# year-led-r1.net
KiCad netlist of a schematic drawn in EAGLE
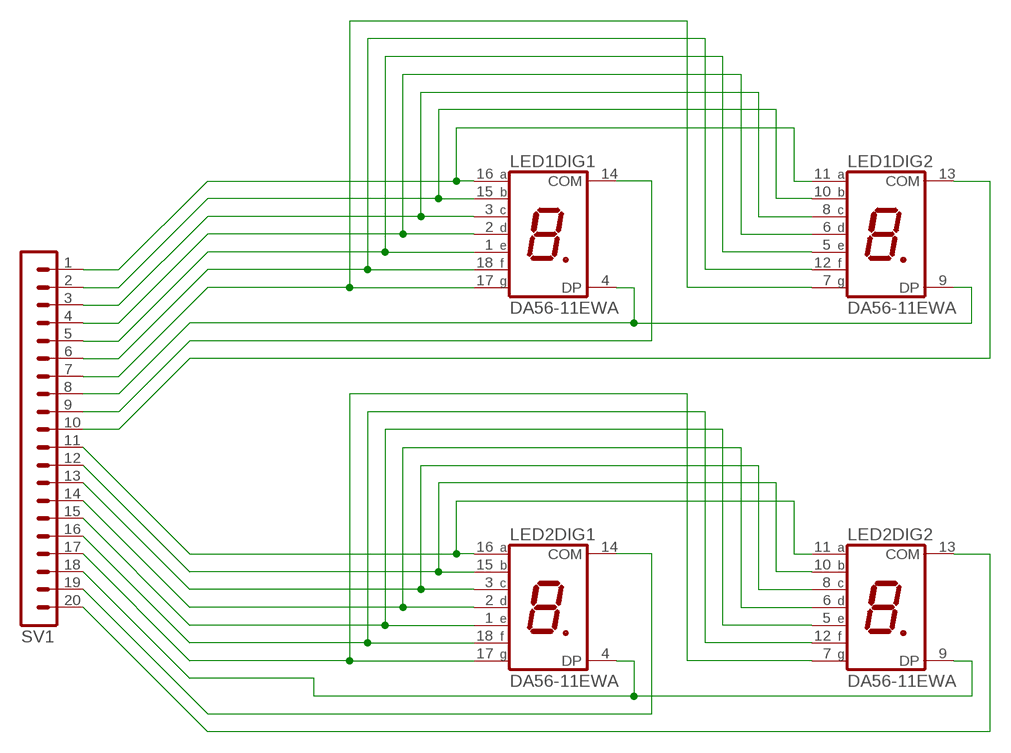
[diagram p0: schematic, sheet 1]

(export (version "E")
  (design (tool "Eeschema 10.0.6"))
  (components
    (comp (ref "LED1")
      (value "DA56-11EWA")
      (footprint "eagle-import:DA56")
      (libsource (lib "eagle-import") (part "DA56-11EWA"))
    )
    (comp (ref "LED2")
      (value "DA56-11EWA")
      (footprint "eagle-import:DA56")
      (libsource (lib "eagle-import") (part "DA56-11EWA"))
    )
    (comp (ref "SV1")
      (value "MA20-1W")
      (footprint "eagle-import:MA20-1W")
      (libsource (lib "eagle-import") (part "MA20-1W"))
    )
  )
  (nets
    (net (code "1") (name "Net-(LED1A-A)") (class "Default")
      (node (ref "LED1") (pin "11") (pinfunction "A_11") (pintype "passive"))
      (node (ref "LED1") (pin "16") (pinfunction "A_16") (pintype "passive"))
      (node (ref "SV1") (pin "1") (pinfunction "1_1") (pintype "passive"))
    )
    (net (code "2") (name "Net-(LED1A-B)") (class "Default")
      (node (ref "LED1") (pin "10") (pinfunction "B_10") (pintype "passive"))
      (node (ref "LED1") (pin "15") (pinfunction "B_15") (pintype "passive"))
      (node (ref "SV1") (pin "2") (pinfunction "2_2") (pintype "passive"))
    )
    (net (code "3") (name "Net-(LED1A-C)") (class "Default")
      (node (ref "LED1") (pin "3") (pinfunction "C_3") (pintype "passive"))
      (node (ref "LED1") (pin "8") (pinfunction "C_8") (pintype "passive"))
      (node (ref "SV1") (pin "3") (pinfunction "3_3") (pintype "passive"))
    )
    (net (code "4") (name "Net-(LED1A-COM)") (class "Default")
      (node (ref "LED1") (pin "14") (pinfunction "COM_14") (pintype "passive"))
      (node (ref "SV1") (pin "9") (pinfunction "9_9") (pintype "passive"))
    )
    (net (code "5") (name "Net-(LED1A-D)") (class "Default")
      (node (ref "LED1") (pin "2") (pinfunction "D_2") (pintype "passive"))
      (node (ref "LED1") (pin "6") (pinfunction "D_6") (pintype "passive"))
      (node (ref "SV1") (pin "4") (pinfunction "4_4") (pintype "passive"))
    )
    (net (code "6") (name "Net-(LED1A-DP)") (class "Default")
      (node (ref "LED1") (pin "4") (pinfunction "DP_4") (pintype "passive"))
      (node (ref "LED1") (pin "9") (pinfunction "DP_9") (pintype "passive"))
      (node (ref "SV1") (pin "8") (pinfunction "8_8") (pintype "passive"))
    )
    (net (code "7") (name "Net-(LED1A-E)") (class "Default")
      (node (ref "LED1") (pin "1") (pinfunction "E_1") (pintype "passive"))
      (node (ref "LED1") (pin "5") (pinfunction "E_5") (pintype "passive"))
      (node (ref "SV1") (pin "5") (pinfunction "5_5") (pintype "passive"))
    )
    (net (code "8") (name "Net-(LED1A-F)") (class "Default")
      (node (ref "LED1") (pin "12") (pinfunction "F_12") (pintype "passive"))
      (node (ref "LED1") (pin "18") (pinfunction "F_18") (pintype "passive"))
      (node (ref "SV1") (pin "6") (pinfunction "6_6") (pintype "passive"))
    )
    (net (code "9") (name "Net-(LED1A-G)") (class "Default")
      (node (ref "LED1") (pin "17") (pinfunction "G_17") (pintype "passive"))
      (node (ref "LED1") (pin "7") (pinfunction "G_7") (pintype "passive"))
      (node (ref "SV1") (pin "7") (pinfunction "7_7") (pintype "passive"))
    )
    (net (code "10") (name "Net-(LED1B-COM)") (class "Default")
      (node (ref "LED1") (pin "13") (pinfunction "COM_13") (pintype "passive"))
      (node (ref "SV1") (pin "10") (pinfunction "10_10") (pintype "passive"))
    )
    (net (code "11") (name "Net-(LED2A-A)") (class "Default")
      (node (ref "LED2") (pin "11") (pinfunction "A_11") (pintype "passive"))
      (node (ref "LED2") (pin "16") (pinfunction "A_16") (pintype "passive"))
      (node (ref "SV1") (pin "11") (pinfunction "11_11") (pintype "passive"))
    )
    (net (code "12") (name "Net-(LED2A-B)") (class "Default")
      (node (ref "LED2") (pin "10") (pinfunction "B_10") (pintype "passive"))
      (node (ref "LED2") (pin "15") (pinfunction "B_15") (pintype "passive"))
      (node (ref "SV1") (pin "12") (pinfunction "12_12") (pintype "passive"))
    )
    (net (code "13") (name "Net-(LED2A-C)") (class "Default")
      (node (ref "LED2") (pin "3") (pinfunction "C_3") (pintype "passive"))
      (node (ref "LED2") (pin "8") (pinfunction "C_8") (pintype "passive"))
      (node (ref "SV1") (pin "13") (pinfunction "13_13") (pintype "passive"))
    )
    (net (code "14") (name "Net-(LED2A-COM)") (class "Default")
      (node (ref "LED2") (pin "14") (pinfunction "COM_14") (pintype "passive"))
      (node (ref "SV1") (pin "19") (pinfunction "19_19") (pintype "passive"))
    )
    (net (code "15") (name "Net-(LED2A-D)") (class "Default")
      (node (ref "LED2") (pin "2") (pinfunction "D_2") (pintype "passive"))
      (node (ref "LED2") (pin "6") (pinfunction "D_6") (pintype "passive"))
      (node (ref "SV1") (pin "14") (pinfunction "14_14") (pintype "passive"))
    )
    (net (code "16") (name "Net-(LED2A-DP)") (class "Default")
      (node (ref "LED2") (pin "4") (pinfunction "DP_4") (pintype "passive"))
      (node (ref "LED2") (pin "9") (pinfunction "DP_9") (pintype "passive"))
      (node (ref "SV1") (pin "18") (pinfunction "18_18") (pintype "passive"))
    )
    (net (code "17") (name "Net-(LED2A-E)") (class "Default")
      (node (ref "LED2") (pin "1") (pinfunction "E_1") (pintype "passive"))
      (node (ref "LED2") (pin "5") (pinfunction "E_5") (pintype "passive"))
      (node (ref "SV1") (pin "15") (pinfunction "15_15") (pintype "passive"))
    )
    (net (code "18") (name "Net-(LED2A-F)") (class "Default")
      (node (ref "LED2") (pin "12") (pinfunction "F_12") (pintype "passive"))
      (node (ref "LED2") (pin "18") (pinfunction "F_18") (pintype "passive"))
      (node (ref "SV1") (pin "16") (pinfunction "16_16") (pintype "passive"))
    )
    (net (code "19") (name "Net-(LED2A-G)") (class "Default")
      (node (ref "LED2") (pin "17") (pinfunction "G_17") (pintype "passive"))
      (node (ref "LED2") (pin "7") (pinfunction "G_7") (pintype "passive"))
      (node (ref "SV1") (pin "17") (pinfunction "17_17") (pintype "passive"))
    )
    (net (code "20") (name "Net-(LED2B-COM)") (class "Default")
      (node (ref "LED2") (pin "13") (pinfunction "COM_13") (pintype "passive"))
      (node (ref "SV1") (pin "20") (pinfunction "20_20") (pintype "passive"))
    )
  )
)
